# TimeCompare.net
KiCad netlist of a schematic drawn in Altium Designer
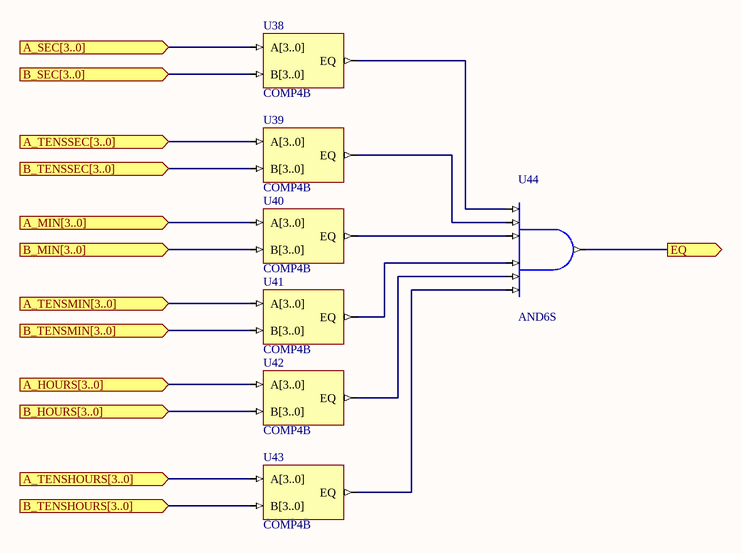
[diagram p0: TimeCompare.SchDoc]

(export (version "E")
  (design (tool "Eeschema 10.0.6"))
  (components
    (comp (ref "U38")
      (value "COMP4B")
      (description "4-Bit Identity Comparator, Bus Version")
      (fields (field (name "PUBLISHER") "Altium Limited"))
      (libsource (lib "FPGA Generic") (part "COMP4B"))
    )
    (comp (ref "U39")
      (value "COMP4B")
      (description "4-Bit Identity Comparator, Bus Version")
      (fields (field (name "PUBLISHER") "Altium Limited"))
      (libsource (lib "FPGA Generic") (part "COMP4B"))
    )
    (comp (ref "U40")
      (value "COMP4B")
      (description "4-Bit Identity Comparator, Bus Version")
      (fields (field (name "PUBLISHER") "Altium Limited"))
      (libsource (lib "FPGA Generic") (part "COMP4B"))
    )
    (comp (ref "U41")
      (value "COMP4B")
      (description "4-Bit Identity Comparator, Bus Version")
      (fields (field (name "PUBLISHER") "Altium Limited"))
      (libsource (lib "FPGA Generic") (part "COMP4B"))
    )
    (comp (ref "U42")
      (value "COMP4B")
      (description "4-Bit Identity Comparator, Bus Version")
      (fields (field (name "PUBLISHER") "Altium Limited"))
      (libsource (lib "FPGA Generic") (part "COMP4B"))
    )
    (comp (ref "U43")
      (value "COMP4B")
      (description "4-Bit Identity Comparator, Bus Version")
      (fields (field (name "PUBLISHER") "Altium Limited"))
      (libsource (lib "FPGA Generic") (part "COMP4B"))
    )
    (comp (ref "U44")
      (value "AND6S")
      (description "6-Input AND Gate, Single Pin Version")
      (fields (field (name "PUBLISHER") "Altium Limited"))
      (libsource (lib "FPGA Generic") (part "AND6S"))
    )
  )
  (nets
    (net (code "49") (name "/A_HOURS[3..0]") (class "Default")
      (node (ref "U42") (pin "A[3..0]") (pinfunction "A[3..0]_A[3..0]") (pintype "input"))
    )
    (net (code "50") (name "/A_MIN[3..0]") (class "Default")
      (node (ref "U40") (pin "A[3..0]") (pinfunction "A[3..0]_A[3..0]") (pintype "input"))
    )
    (net (code "51") (name "/A_SEC[3..0]") (class "Default")
      (node (ref "U38") (pin "A[3..0]") (pinfunction "A[3..0]_A[3..0]") (pintype "input"))
    )
    (net (code "52") (name "/A_TENSHOURS[3..0]") (class "Default")
      (node (ref "U43") (pin "A[3..0]") (pinfunction "A[3..0]_A[3..0]") (pintype "input"))
    )
    (net (code "53") (name "/A_TENSMIN[3..0]") (class "Default")
      (node (ref "U41") (pin "A[3..0]") (pinfunction "A[3..0]_A[3..0]") (pintype "input"))
    )
    (net (code "54") (name "/A_TENSSEC[3..0]") (class "Default")
      (node (ref "U39") (pin "A[3..0]") (pinfunction "A[3..0]_A[3..0]") (pintype "input"))
    )
    (net (code "55") (name "/B_HOURS[3..0]") (class "Default")
      (node (ref "U42") (pin "B[3..0]") (pinfunction "B[3..0]_B[3..0]") (pintype "input"))
    )
    (net (code "56") (name "/B_MIN[3..0]") (class "Default")
      (node (ref "U40") (pin "B[3..0]") (pinfunction "B[3..0]_B[3..0]") (pintype "input"))
    )
    (net (code "57") (name "/B_SEC[3..0]") (class "Default")
      (node (ref "U38") (pin "B[3..0]") (pinfunction "B[3..0]_B[3..0]") (pintype "input"))
    )
    (net (code "58") (name "/B_TENSHOURS[3..0]") (class "Default")
      (node (ref "U43") (pin "B[3..0]") (pinfunction "B[3..0]_B[3..0]") (pintype "input"))
    )
    (net (code "59") (name "/B_TENSMIN[3..0]") (class "Default")
      (node (ref "U41") (pin "B[3..0]") (pinfunction "B[3..0]_B[3..0]") (pintype "input"))
    )
    (net (code "60") (name "/B_TENSSEC[3..0]") (class "Default")
      (node (ref "U39") (pin "B[3..0]") (pinfunction "B[3..0]_B[3..0]") (pintype "input"))
    )
    (net (code "61") (name "/EQ") (class "Default")
      (node (ref "U44") (pin "O") (pinfunction "O_O") (pintype "output"))
    )
    (net (code "62") (name "Net-(U38-PadEQ)") (class "Default")
      (node (ref "U38") (pin "EQ") (pinfunction "EQ_EQ") (pintype "output"))
      (node (ref "U44") (pin "I0") (pinfunction "I0_I0") (pintype "input"))
    )
    (net (code "63") (name "Net-(U39-PadEQ)") (class "Default")
      (node (ref "U39") (pin "EQ") (pinfunction "EQ_EQ") (pintype "output"))
      (node (ref "U44") (pin "I1") (pinfunction "I1_I1") (pintype "input"))
    )
    (net (code "64") (name "Net-(U40-PadEQ)") (class "Default")
      (node (ref "U40") (pin "EQ") (pinfunction "EQ_EQ") (pintype "output"))
      (node (ref "U44") (pin "I2") (pinfunction "I2_I2") (pintype "input"))
    )
    (net (code "65") (name "Net-(U41-PadEQ)") (class "Default")
      (node (ref "U41") (pin "EQ") (pinfunction "EQ_EQ") (pintype "output"))
      (node (ref "U44") (pin "I3") (pinfunction "I3_I3") (pintype "input"))
    )
    (net (code "66") (name "Net-(U42-PadEQ)") (class "Default")
      (node (ref "U42") (pin "EQ") (pinfunction "EQ_EQ") (pintype "output"))
      (node (ref "U44") (pin "I4") (pinfunction "I4_I4") (pintype "input"))
    )
    (net (code "67") (name "Net-(U43-PadEQ)") (class "Default")
      (node (ref "U43") (pin "EQ") (pinfunction "EQ_EQ") (pintype "output"))
      (node (ref "U44") (pin "I5") (pinfunction "I5_I5") (pintype "input"))
    )
  )
)
